# hail.net
KiCad netlist of a schematic drawn in EAGLE
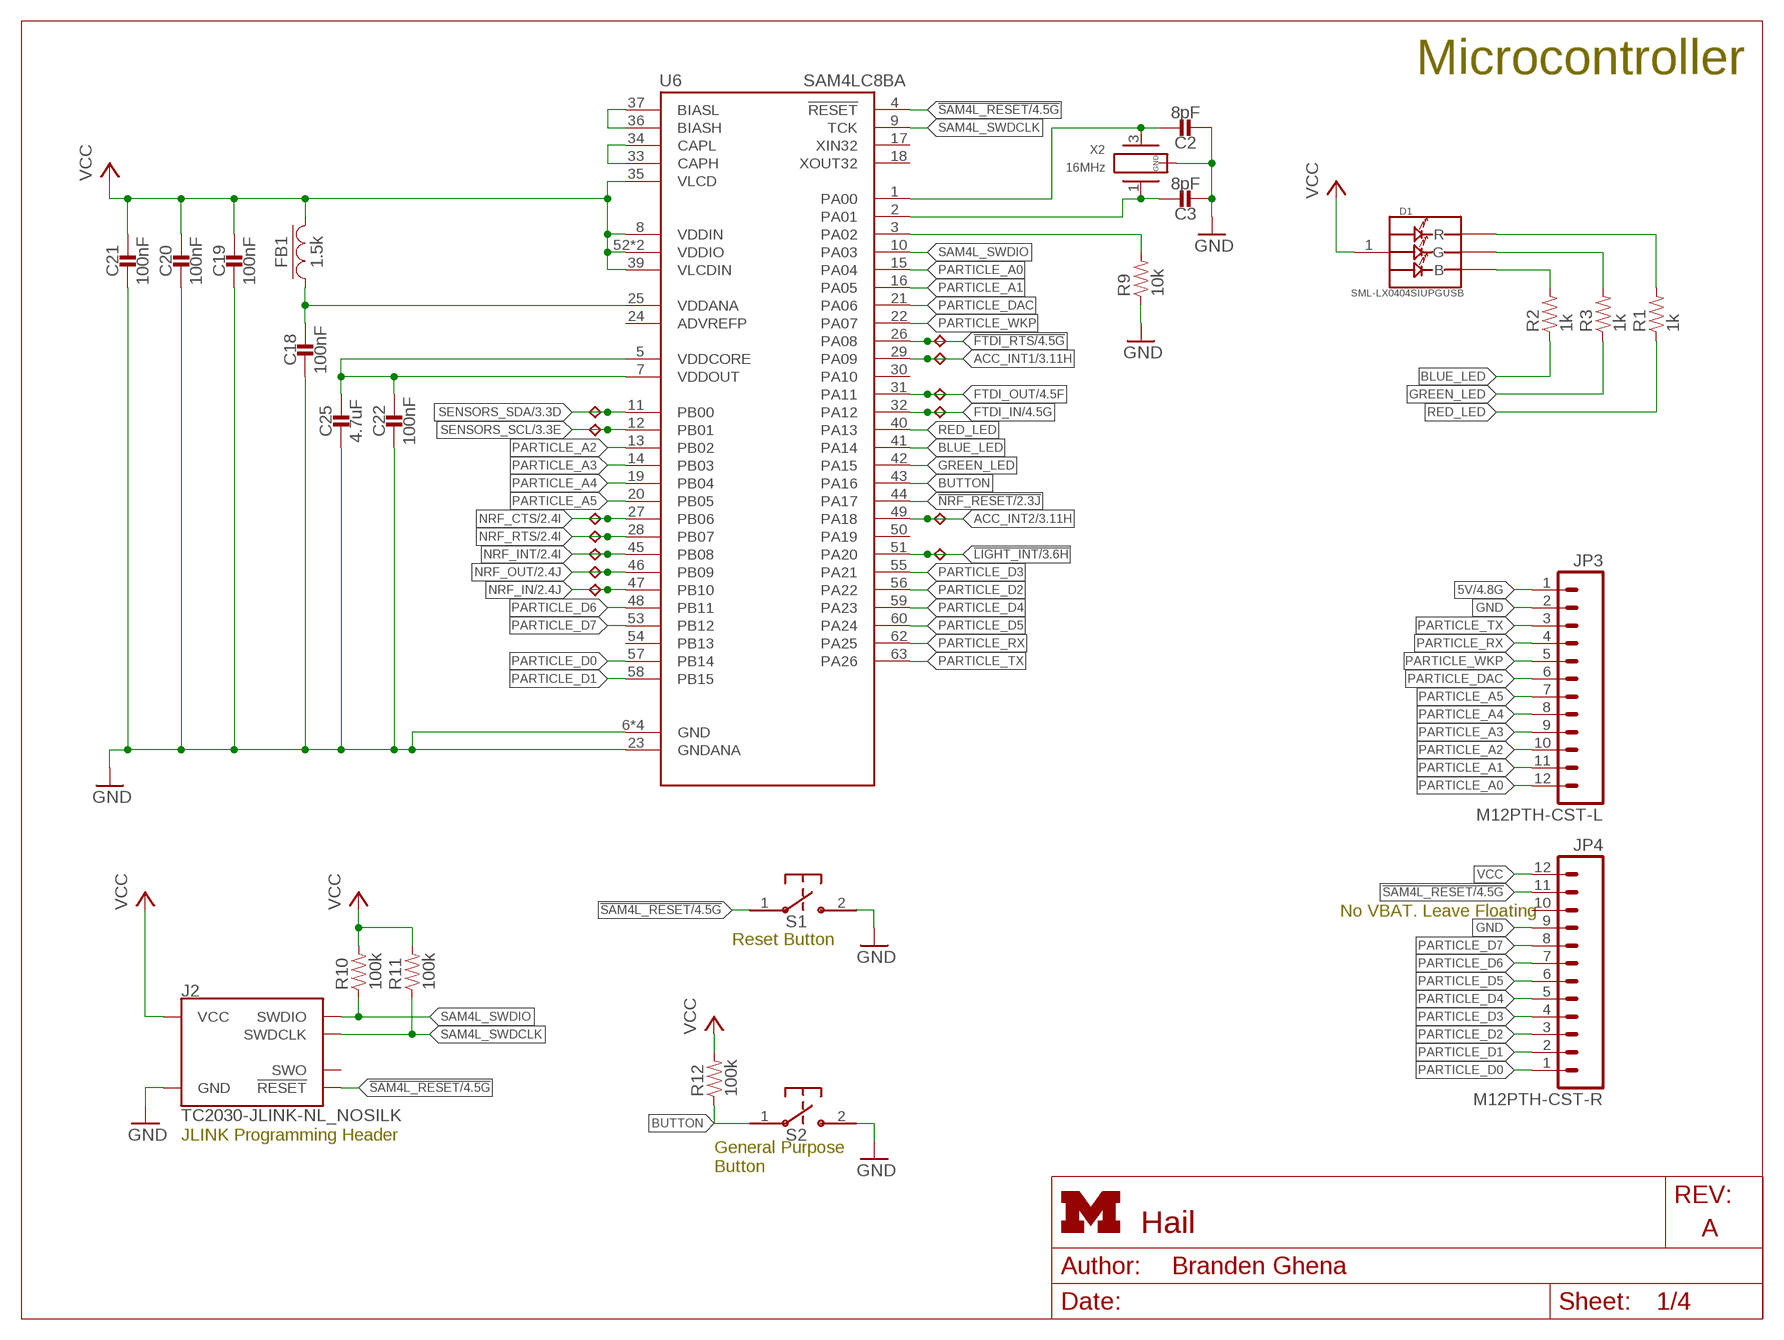
[diagram p0: schematic, sheet 1]
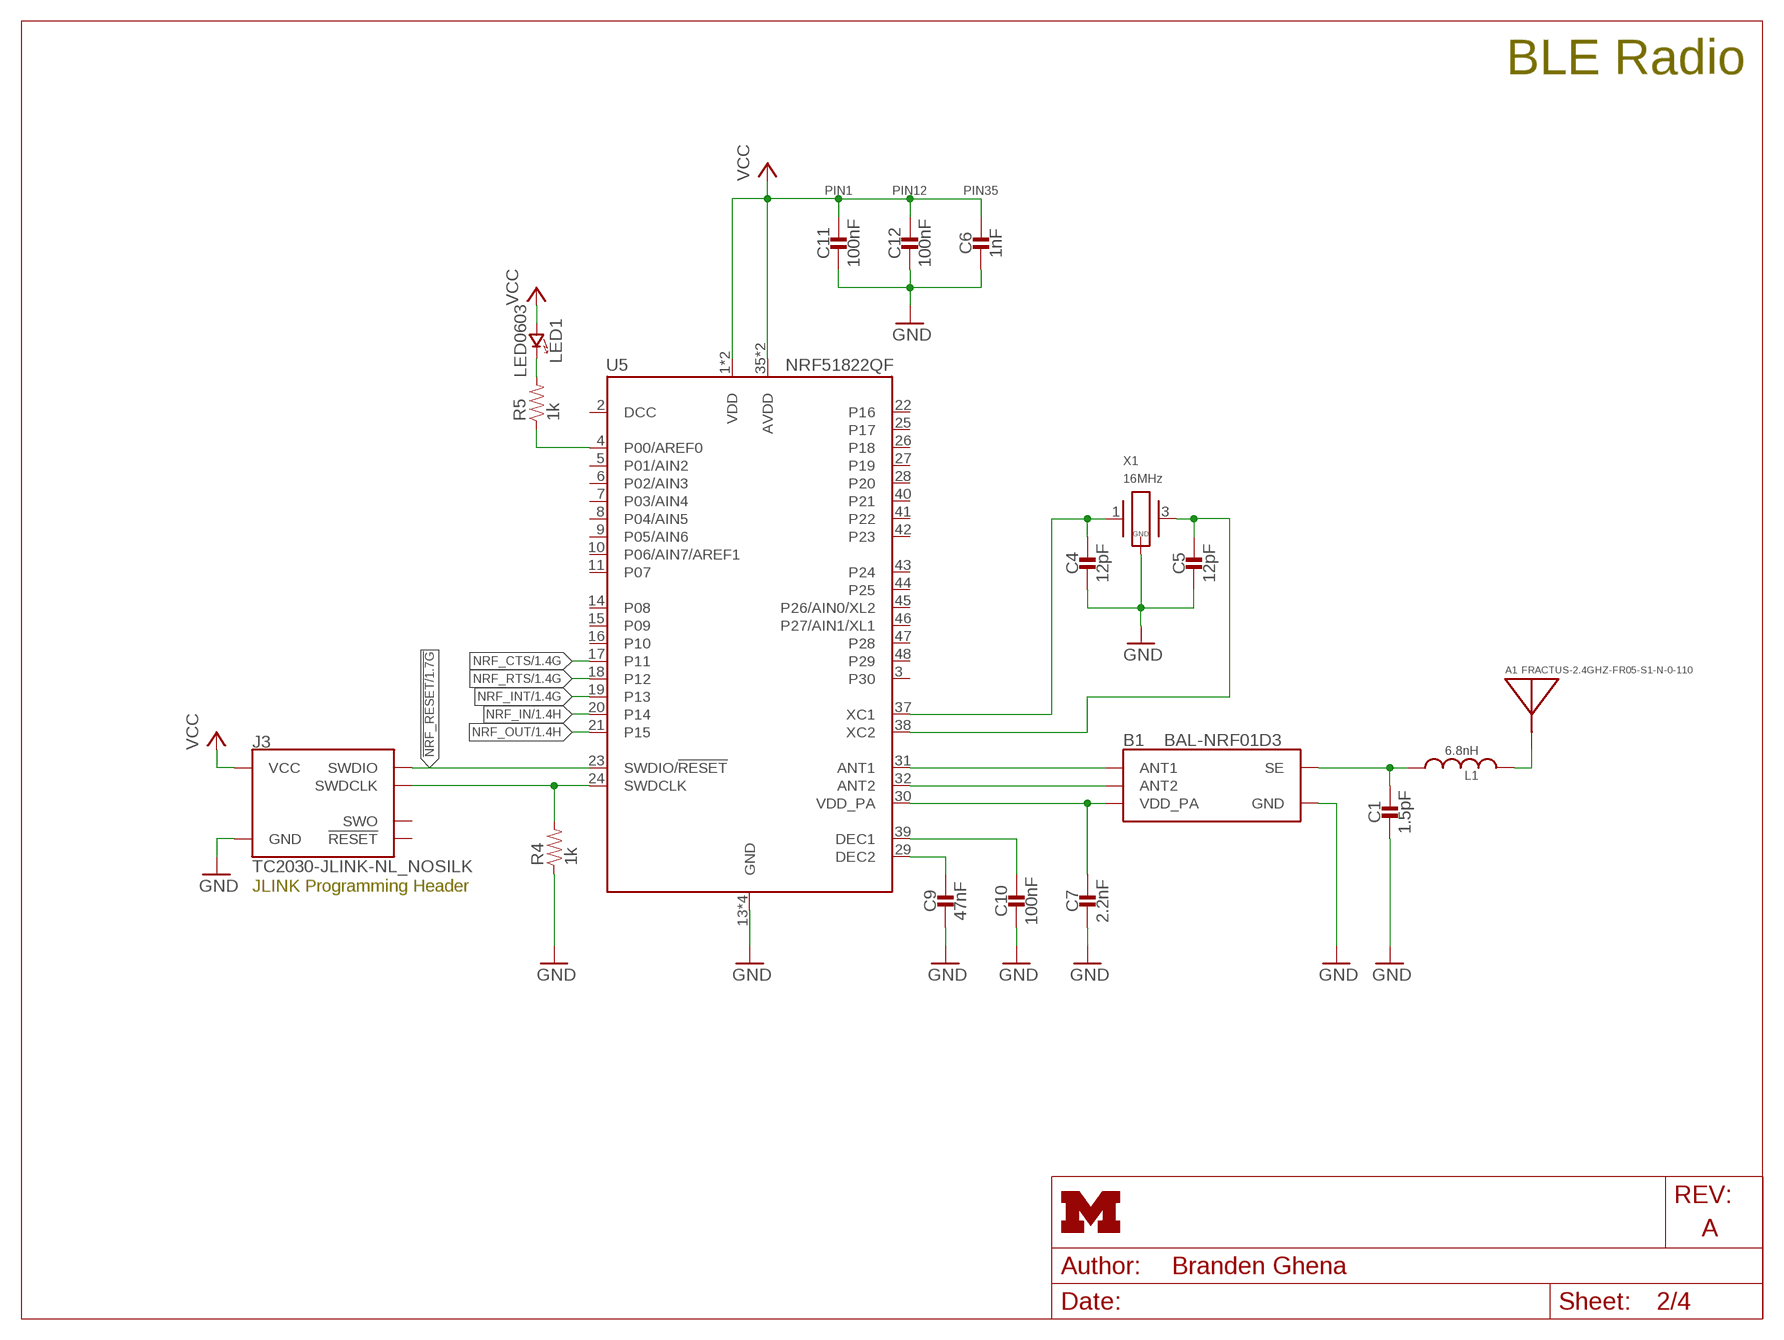
[diagram p1: schematic, sheet 2]
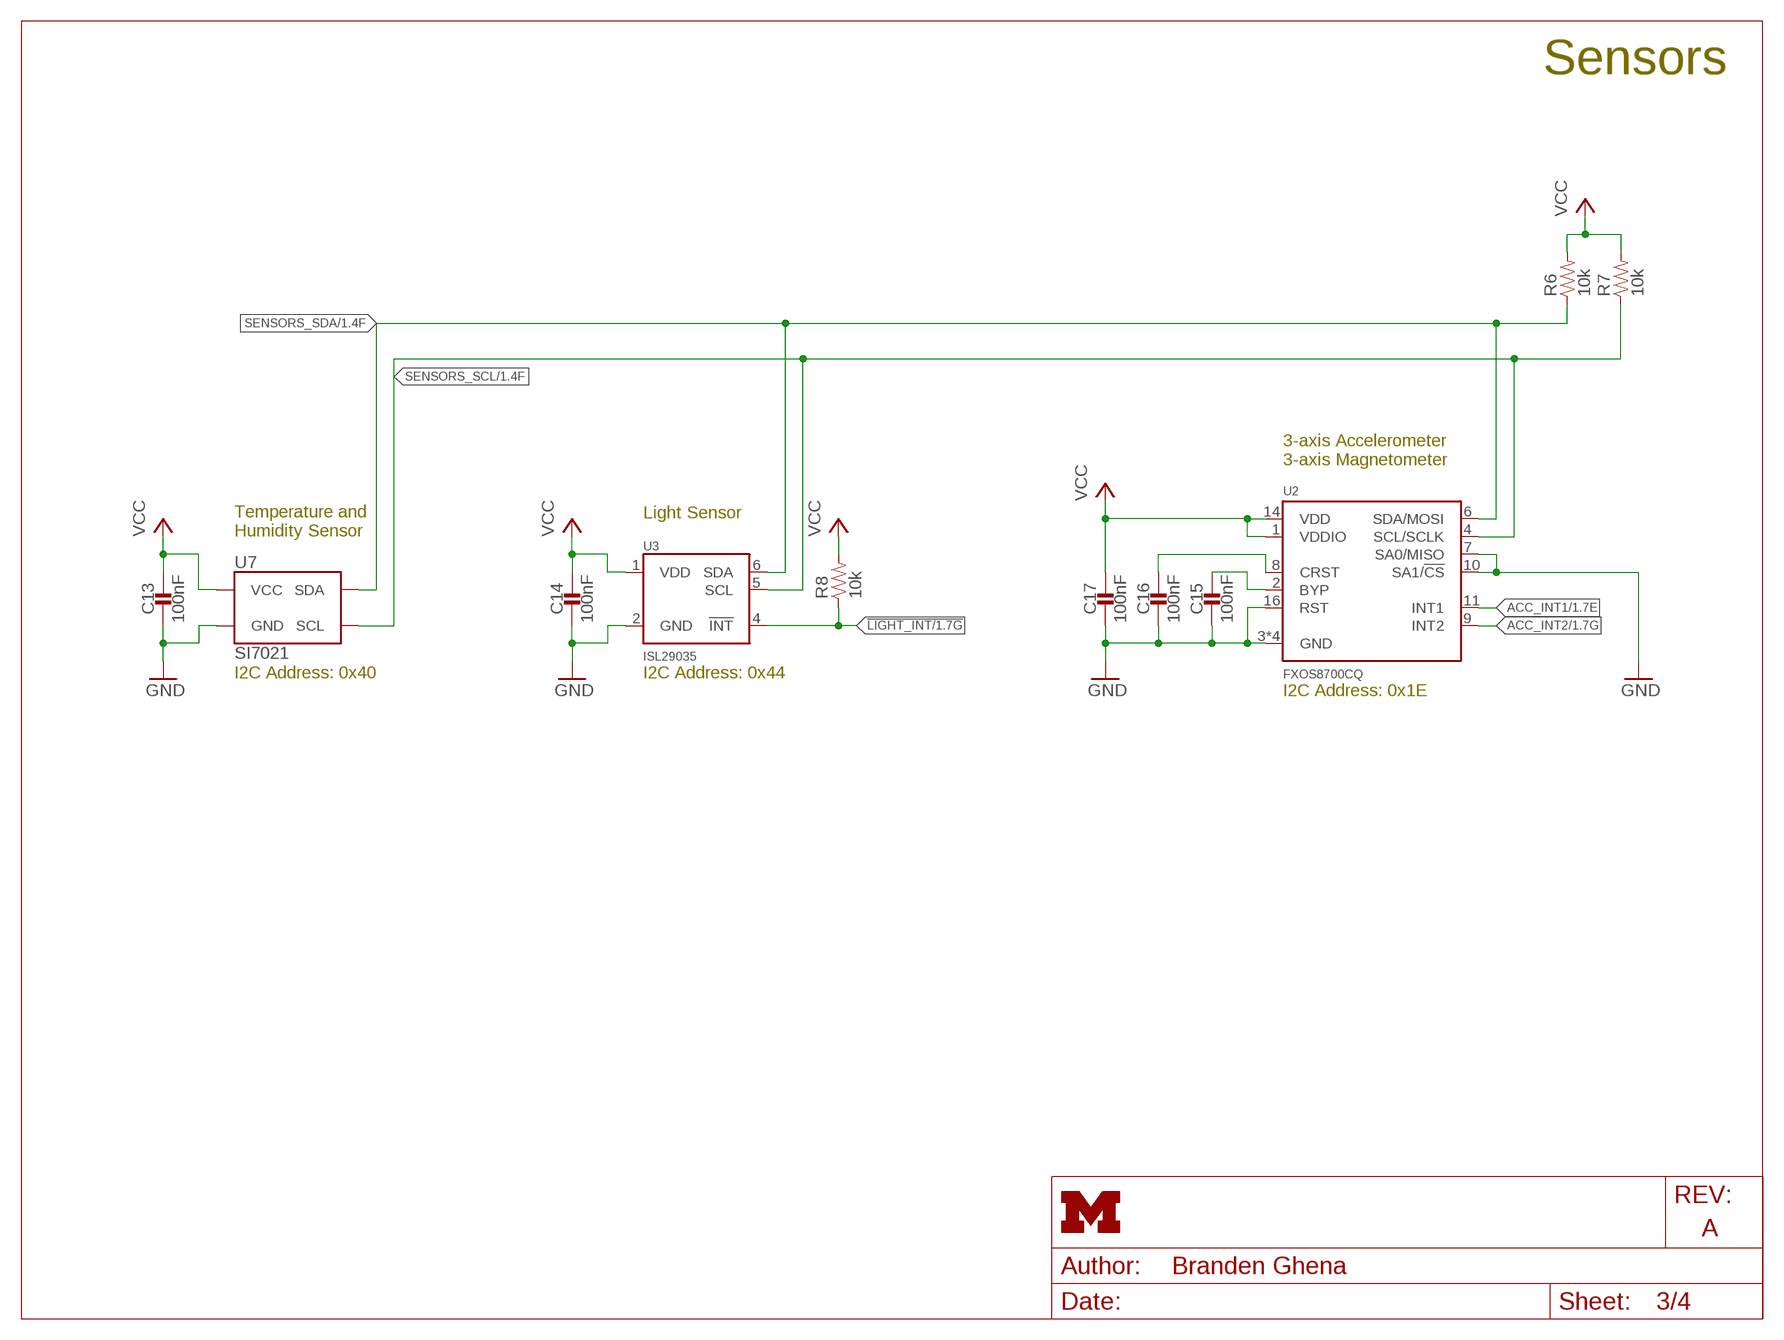
[diagram p2: schematic, sheet 3]
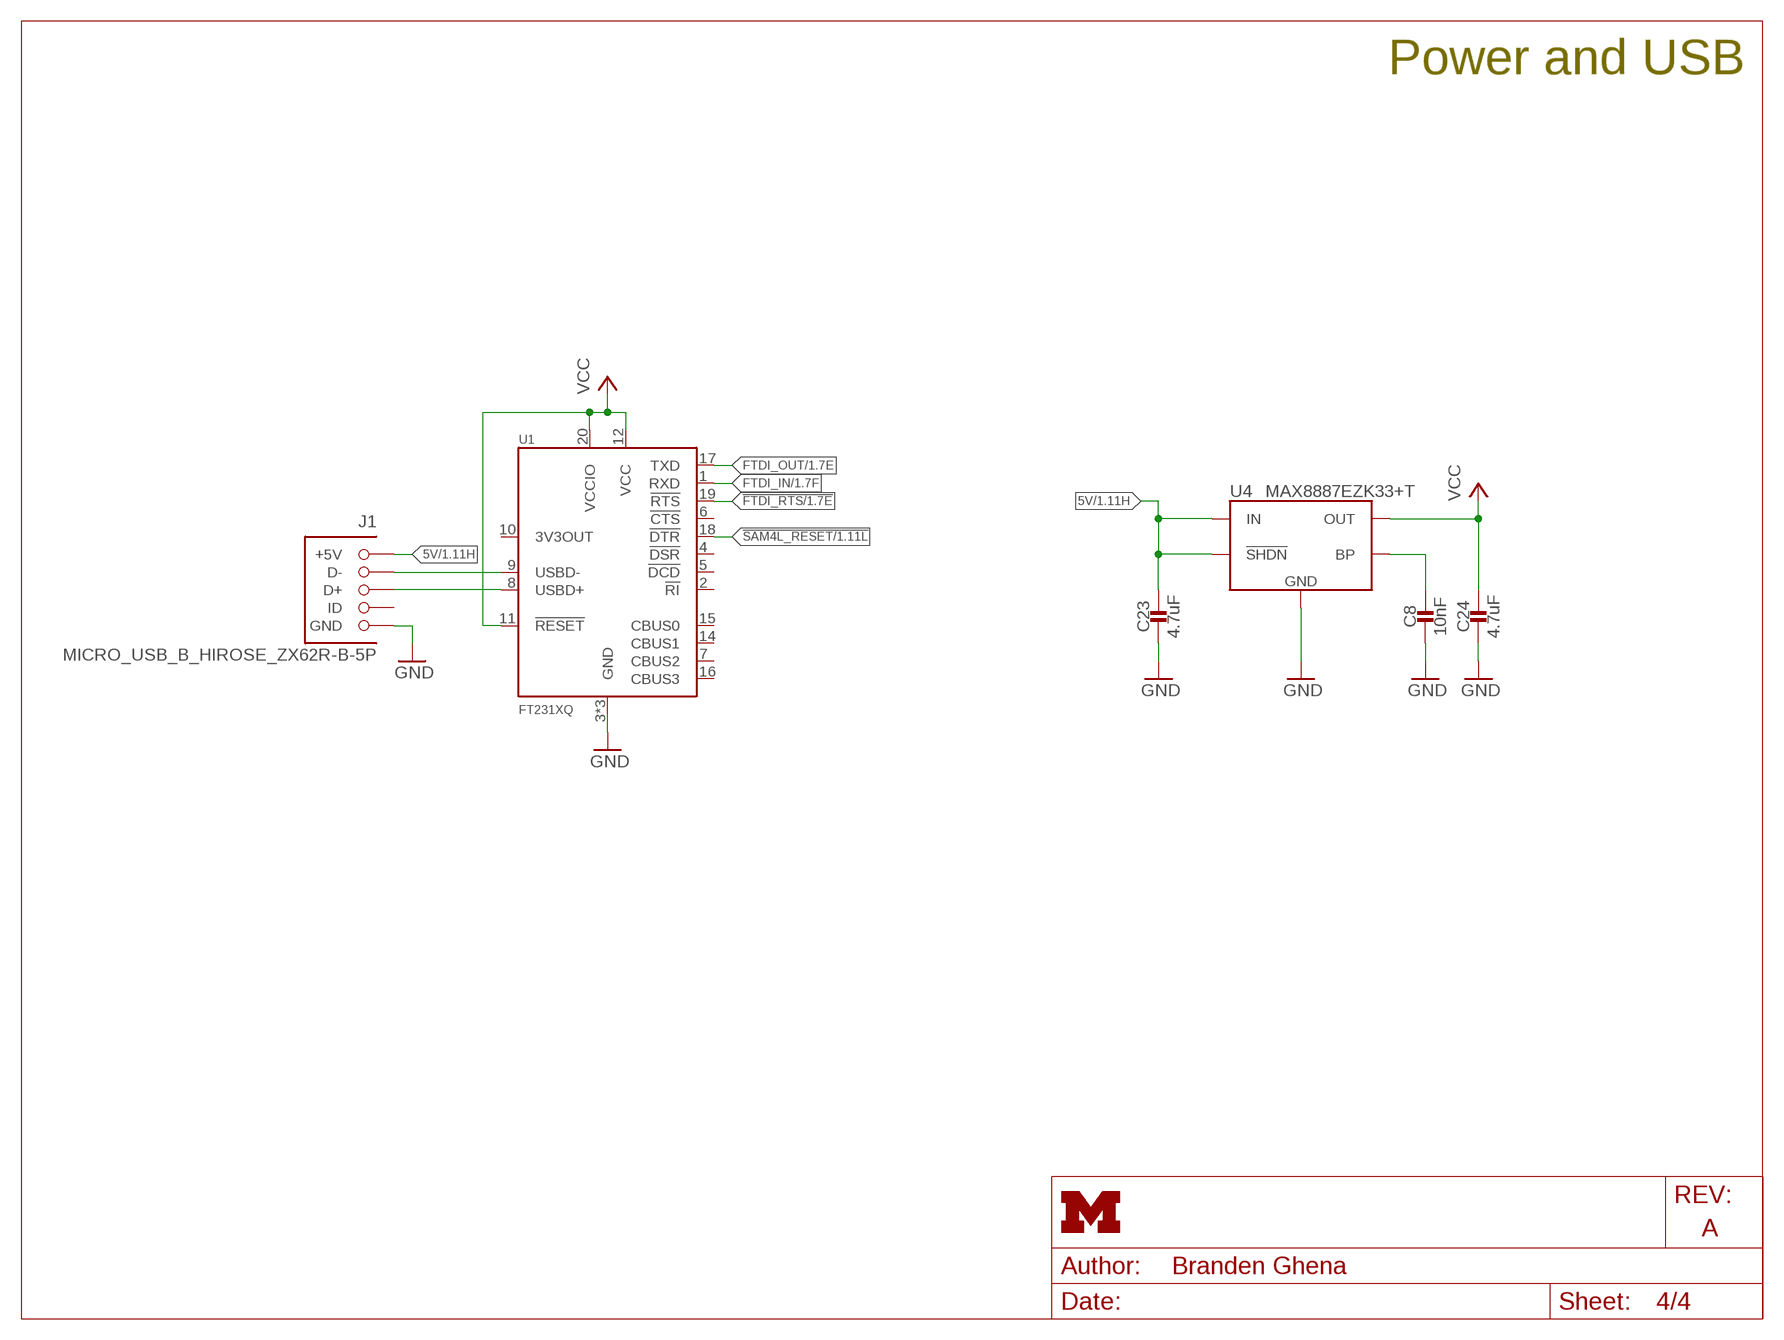
[diagram p3: schematic, sheet 4]

(export (version "E")
  (design (tool "Eeschema 10.0.6"))
  (components
    (comp (ref "C2")
      (value "8pF")
      (footprint "eagle-import:0402_CAP")
      (libsource (lib "eagle-import") (part "CAPACITOR0402_CAP"))
    )
    (comp (ref "C3")
      (value "8pF")
      (footprint "eagle-import:0402_CAP")
      (libsource (lib "eagle-import") (part "CAPACITOR0402_CAP"))
    )
    (comp (ref "C18")
      (value "100nF")
      (footprint "eagle-import:0402_CAP")
      (libsource (lib "eagle-import") (part "CAPACITOR0402_CAP"))
    )
    (comp (ref "C19")
      (value "100nF")
      (footprint "eagle-import:0402_CAP")
      (libsource (lib "eagle-import") (part "CAPACITOR0402_CAP"))
    )
    (comp (ref "C20")
      (value "100nF")
      (footprint "eagle-import:0402_CAP")
      (libsource (lib "eagle-import") (part "CAPACITOR0402_CAP"))
    )
    (comp (ref "C21")
      (value "100nF")
      (footprint "eagle-import:0402_CAP")
      (libsource (lib "eagle-import") (part "CAPACITOR0402_CAP"))
    )
    (comp (ref "C22")
      (value "100nF")
      (footprint "eagle-import:0402_CAP")
      (libsource (lib "eagle-import") (part "CAPACITOR0402_CAP"))
    )
    (comp (ref "C25")
      (value "4.7uF")
      (footprint "eagle-import:0402_CAP")
      (libsource (lib "eagle-import") (part "CAPACITOR0402_CAP"))
    )
    (comp (ref "D1")
      (value "SML-LX0404SIUPGUSB")
      (footprint "eagle-import:1MM_SQ_4PAD")
      (libsource (lib "eagle-import") (part "SML-LX0404SIUPGUSB"))
    )
    (comp (ref "FB1")
      (value "1.5k")
      (footprint "eagle-import:0402_CAP")
      (libsource (lib "eagle-import") (part "FERRITE_BEAD0402"))
    )
    (comp (ref "J2")
      (value "TC2030-JLINK-NL_NOSILK")
      (footprint "eagle-import:TC2030-IDC-NL_NOSILK")
      (libsource (lib "eagle-import") (part "TC2030-JLINK-NL_NOSILK"))
    )
    (comp (ref "JP3")
      (value "M12PTH-CST-L")
      (footprint "eagle-import:1X12-CASTELLATED")
      (libsource (lib "eagle-import") (part "M12PTH-CST-L"))
    )
    (comp (ref "JP4")
      (value "M12PTH-CST-R")
      (footprint "eagle-import:1X12-CASTELLATED")
      (libsource (lib "eagle-import") (part "M12PTH-CST-R"))
    )
    (comp (ref "R1")
      (value "1k")
      (footprint "eagle-import:0402_RES")
      (libsource (lib "eagle-import") (part "RESISTOR0402_RES"))
    )
    (comp (ref "R2")
      (value "1k")
      (footprint "eagle-import:0402_RES")
      (libsource (lib "eagle-import") (part "RESISTOR0402_RES"))
    )
    (comp (ref "R3")
      (value "1k")
      (footprint "eagle-import:0402_RES")
      (libsource (lib "eagle-import") (part "RESISTOR0402_RES"))
    )
    (comp (ref "R9")
      (value "10k")
      (footprint "eagle-import:0402_RES")
      (libsource (lib "eagle-import") (part "RESISTOR0402_RES"))
    )
    (comp (ref "R10")
      (value "100k")
      (footprint "eagle-import:0402_RES")
      (libsource (lib "eagle-import") (part "RESISTOR0402_RES"))
    )
    (comp (ref "R11")
      (value "100k")
      (footprint "eagle-import:0402_RES")
      (libsource (lib "eagle-import") (part "RESISTOR0402_RES"))
    )
    (comp (ref "R12")
      (value "100k")
      (footprint "eagle-import:0402_RES")
      (libsource (lib "eagle-import") (part "RESISTOR0402_RES"))
    )
    (comp (ref "S1")
      (value "B3U-1000P")
      (footprint "eagle-import:B3U-1000P")
      (libsource (lib "eagle-import") (part "B3U-1000P"))
    )
    (comp (ref "S2")
      (value "B3U-1000P")
      (footprint "eagle-import:B3U-1000P")
      (libsource (lib "eagle-import") (part "B3U-1000P"))
    )
    (comp (ref "TP1")
      (value "TPB1,27")
      (footprint "eagle-import:B1,27")
      (libsource (lib "eagle-import") (part "TPB1,27"))
    )
    (comp (ref "TP2")
      (value "TPB1,27")
      (footprint "eagle-import:B1,27")
      (libsource (lib "eagle-import") (part "TPB1,27"))
    )
    (comp (ref "TP3")
      (value "TPB1,27")
      (footprint "eagle-import:B1,27")
      (libsource (lib "eagle-import") (part "TPB1,27"))
    )
    (comp (ref "TP4")
      (value "TPB1,27")
      (footprint "eagle-import:B1,27")
      (libsource (lib "eagle-import") (part "TPB1,27"))
    )
    (comp (ref "TP5")
      (value "TPB1,27")
      (footprint "eagle-import:B1,27")
      (libsource (lib "eagle-import") (part "TPB1,27"))
    )
    (comp (ref "TP6")
      (value "TPB1,27")
      (footprint "eagle-import:B1,27")
      (libsource (lib "eagle-import") (part "TPB1,27"))
    )
    (comp (ref "TP7")
      (value "TPB1,27")
      (footprint "eagle-import:B1,27")
      (libsource (lib "eagle-import") (part "TPB1,27"))
    )
    (comp (ref "TP8")
      (value "TPB1,27")
      (footprint "eagle-import:B1,27")
      (libsource (lib "eagle-import") (part "TPB1,27"))
    )
    (comp (ref "TP9")
      (value "TPB1,27")
      (footprint "eagle-import:B1,27")
      (libsource (lib "eagle-import") (part "TPB1,27"))
    )
    (comp (ref "TP10")
      (value "TPB1,27")
      (footprint "eagle-import:B1,27")
      (libsource (lib "eagle-import") (part "TPB1,27"))
    )
    (comp (ref "TP11")
      (value "TPB1,27")
      (footprint "eagle-import:B1,27")
      (libsource (lib "eagle-import") (part "TPB1,27"))
    )
    (comp (ref "TP12")
      (value "TPB1,27")
      (footprint "eagle-import:B1,27")
      (libsource (lib "eagle-import") (part "TPB1,27"))
    )
    (comp (ref "TP13")
      (value "TPB1,27")
      (footprint "eagle-import:B1,27")
      (libsource (lib "eagle-import") (part "TPB1,27"))
    )
    (comp (ref "U6")
      (value "SAM4LC8BA")
      (footprint "eagle-import:QFN-64-9MM")
      (fields (field (name "DIGIKEY") "ATSAM4LC8BA-MURCT-ND"))
      (libsource (lib "eagle-import") (part "SAM4LC8BA"))
    )
    (comp (ref "X2")
      (value "16MHz")
      (footprint "eagle-import:FHXXX")
      (libsource (lib "eagle-import") (part "FH1600015"))
    )
    (comp (ref "A1")
      (value "FRACTUS-2.4GHZ-FR05-S1-N-0-110")
      (footprint "eagle-import:FRACTUS-ANTENNA-FR05-S1-N-0-110")
      (libsource (lib "eagle-import") (part "FRACTUS-2.4GHZ-FR05-S1-N-0-110"))
    )
    (comp (ref "B1")
      (value "BAL-NRF01D3")
      (footprint "eagle-import:BAL-NRF01D3")
      (libsource (lib "eagle-import") (part "BAL-NRF01D3"))
    )
    (comp (ref "C1")
      (value "1.5pF")
      (footprint "eagle-import:0402_CAP")
      (libsource (lib "eagle-import") (part "CAPACITOR0402_CAP"))
    )
    (comp (ref "C4")
      (value "12pF")
      (footprint "eagle-import:0402_CAP")
      (libsource (lib "eagle-import") (part "CAPACITOR0402_CAP"))
    )
    (comp (ref "C5")
      (value "12pF")
      (footprint "eagle-import:0402_CAP")
      (libsource (lib "eagle-import") (part "CAPACITOR0402_CAP"))
    )
    (comp (ref "C6")
      (value "1nF")
      (footprint "eagle-import:0402_CAP")
      (libsource (lib "eagle-import") (part "CAPACITOR0402_CAP"))
    )
    (comp (ref "C7")
      (value "2.2nF")
      (footprint "eagle-import:0402_CAP")
      (libsource (lib "eagle-import") (part "CAPACITOR0402_CAP"))
    )
    (comp (ref "C9")
      (value "47nF")
      (footprint "eagle-import:0402_CAP")
      (libsource (lib "eagle-import") (part "CAPACITOR0402_CAP"))
    )
    (comp (ref "C10")
      (value "100nF")
      (footprint "eagle-import:0402_CAP")
      (libsource (lib "eagle-import") (part "CAPACITOR0402_CAP"))
    )
    (comp (ref "C11")
      (value "100nF")
      (footprint "eagle-import:0402_CAP")
      (libsource (lib "eagle-import") (part "CAPACITOR0402_CAP"))
    )
    (comp (ref "C12")
      (value "100nF")
      (footprint "eagle-import:0402_CAP")
      (libsource (lib "eagle-import") (part "CAPACITOR0402_CAP"))
    )
    (comp (ref "J3")
      (value "TC2030-JLINK-NL_NOSILK")
      (footprint "eagle-import:TC2030-IDC-NL_NOSILK")
      (libsource (lib "eagle-import") (part "TC2030-JLINK-NL_NOSILK"))
    )
    (comp (ref "L1")
      (value "6.8nH")
      (footprint "eagle-import:0402_CAP")
      (libsource (lib "eagle-import") (part "INDUCTOR0402"))
    )
    (comp (ref "LED1")
      (value "LED0603")
      (footprint "eagle-import:LED-0603")
      (libsource (lib "eagle-import") (part "LED0603"))
    )
    (comp (ref "R4")
      (value "1k")
      (footprint "eagle-import:0402_RES")
      (libsource (lib "eagle-import") (part "RESISTOR0402_RES"))
    )
    (comp (ref "R5")
      (value "1k")
      (footprint "eagle-import:0402_RES")
      (libsource (lib "eagle-import") (part "RESISTOR0402_RES"))
    )
    (comp (ref "U5")
      (value "NRF51822QF")
      (footprint "eagle-import:QFN-48-6MM")
      (fields (field (name "DIGIKEY") "1490-1049-1-ND"))
      (libsource (lib "eagle-import") (part "NRF51822QF"))
    )
    (comp (ref "X1")
      (value "16MHz")
      (footprint "eagle-import:TXC-8Y")
      (libsource (lib "eagle-import") (part "TXC-8Y"))
    )
    (comp (ref "C8")
      (value "10nF")
      (footprint "eagle-import:0402_CAP")
      (libsource (lib "eagle-import") (part "CAPACITOR0402_CAP"))
    )
    (comp (ref "C23")
      (value "4.7uF")
      (footprint "eagle-import:0402_CAP")
      (libsource (lib "eagle-import") (part "CAPACITOR0402_CAP"))
    )
    (comp (ref "C24")
      (value "4.7uF")
      (footprint "eagle-import:0402_CAP")
      (libsource (lib "eagle-import") (part "CAPACITOR0402_CAP"))
    )
    (comp (ref "J1")
      (value "MICRO_USB_B_HIROSE_ZX62R-B-5P")
      (footprint "eagle-import:USB_MICRO_B-HIROSE-ZX62R-B-5P")
      (fields (field (name "DIGIKEY") "H125274CT-ND"))
      (libsource (lib "eagle-import") (part "MICRO_USB_B_HIROSE_ZX62R-B-5P"))
    )
    (comp (ref "U1")
      (value "FT231XQ")
      (footprint "eagle-import:QFN-20-4MM")
      (fields (field (name "MPN") "FT231XQ-R"))
      (libsource (lib "eagle-import") (part "FT231XQ"))
    )
    (comp (ref "U4")
      (value "MAX8887EZK33+T")
      (footprint "eagle-import:SOT-23-5")
      (libsource (lib "eagle-import") (part "MAX8887EZK33+T"))
    )
    (comp (ref "C13")
      (value "100nF")
      (footprint "eagle-import:0402_CAP")
      (libsource (lib "eagle-import") (part "CAPACITOR0402_CAP"))
    )
    (comp (ref "C14")
      (value "100nF")
      (footprint "eagle-import:0402_CAP")
      (libsource (lib "eagle-import") (part "CAPACITOR0402_CAP"))
    )
    (comp (ref "C15")
      (value "100nF")
      (footprint "eagle-import:0402_CAP")
      (libsource (lib "eagle-import") (part "CAPACITOR0402_CAP"))
    )
    (comp (ref "C16")
      (value "100nF")
      (footprint "eagle-import:0402_CAP")
      (libsource (lib "eagle-import") (part "CAPACITOR0402_CAP"))
    )
    (comp (ref "C17")
      (value "100nF")
      (footprint "eagle-import:0402_CAP")
      (libsource (lib "eagle-import") (part "CAPACITOR0402_CAP"))
    )
    (comp (ref "R6")
      (value "10k")
      (footprint "eagle-import:0402_RES")
      (libsource (lib "eagle-import") (part "RESISTOR0402_RES"))
    )
    (comp (ref "R7")
      (value "10k")
      (footprint "eagle-import:0402_RES")
      (libsource (lib "eagle-import") (part "RESISTOR0402_RES"))
    )
    (comp (ref "R8")
      (value "10k")
      (footprint "eagle-import:0402_RES")
      (libsource (lib "eagle-import") (part "RESISTOR0402_RES"))
    )
    (comp (ref "U2")
      (value "FXOS8700CQ")
      (footprint "eagle-import:QFN-16-3MM")
      (fields (field (name "MPN") "FXOS8700CQR1"))
      (libsource (lib "eagle-import") (part "FXOS8700CQ"))
    )
    (comp (ref "U3")
      (value "ISL29035")
      (footprint "eagle-import:ODFN-6-1.5MMX1.6MM")
      (fields (field (name "MPN") "ISL29035IROZ-T7"))
      (libsource (lib "eagle-import") (part "ISL29035"))
    )
    (comp (ref "U7")
      (value "SI7021")
      (footprint "eagle-import:DFN-6_3MM")
      (fields (field (name "DIGIKEY") "336-3141-ND"))
      (libsource (lib "eagle-import") (part "SI7021"))
    )
  )
  (nets
    (net (code "1") (name "5V") (class "Default")
      (node (ref "C23") (pin "1") (pinfunction "1_1") (pintype "bidirectional"))
      (node (ref "J1") (pin "1") (pinfunction "+5V_1") (pintype "bidirectional"))
      (node (ref "JP3") (pin "1") (pinfunction "12_1") (pintype "passive"))
      (node (ref "U4") (pin "1") (pinfunction "IN_1") (pintype "bidirectional"))
      (node (ref "U4") (pin "3") (pinfunction "~{SHDN}_3") (pintype "bidirectional"))
    )
    (net (code "2") (name "ACC_INT1") (class "Default")
      (node (ref "TP8") (pin "TP") (pinfunction "TP_TP") (pintype "input"))
      (node (ref "U2") (pin "11") (pinfunction "INT1_11") (pintype "bidirectional"))
      (node (ref "U6") (pin "29") (pinfunction "PA09_29") (pintype "bidirectional"))
    )
    (net (code "3") (name "ACC_INT2") (class "Default")
      (node (ref "TP9") (pin "TP") (pinfunction "TP_TP") (pintype "input"))
      (node (ref "U2") (pin "9") (pinfunction "INT2_9") (pintype "bidirectional"))
      (node (ref "U6") (pin "49") (pinfunction "PA18_49") (pintype "bidirectional"))
    )
    (net (code "4") (name "ADVREFP") (class "Default")
      (node (ref "U6") (pin "24") (pinfunction "ADVREFP_24") (pintype "power_in"))
    )
    (net (code "5") (name "BLUE_LED") (class "Default")
      (node (ref "R2") (pin "1") (pinfunction "1_1") (pintype "passive"))
      (node (ref "U6") (pin "41") (pinfunction "PA14_41") (pintype "bidirectional"))
    )
    (net (code "6") (name "BUTTON") (class "Default")
      (node (ref "R12") (pin "1") (pinfunction "1_1") (pintype "passive"))
      (node (ref "S2") (pin "1") (pinfunction "P$1_1") (pintype "passive"))
      (node (ref "U6") (pin "43") (pinfunction "PA16_43") (pintype "bidirectional"))
    )
    (net (code "7") (name "FTDI_IN") (class "Default")
      (node (ref "TP13") (pin "TP") (pinfunction "TP_TP") (pintype "input"))
      (node (ref "U1") (pin "1") (pinfunction "RXD_1") (pintype "bidirectional"))
      (node (ref "U6") (pin "32") (pinfunction "PA12_32") (pintype "bidirectional"))
    )
    (net (code "8") (name "FTDI_OUT") (class "Default")
      (node (ref "TP12") (pin "TP") (pinfunction "TP_TP") (pintype "input"))
      (node (ref "U1") (pin "17") (pinfunction "TXD_17") (pintype "bidirectional"))
      (node (ref "U6") (pin "31") (pinfunction "PA11_31") (pintype "bidirectional"))
    )
    (net (code "9") (name "GND") (class "Default")
      (node (ref "B1") (pin "GND") (pinfunction "GND_GND") (pintype "bidirectional"))
      (node (ref "C1") (pin "2") (pinfunction "2_2") (pintype "bidirectional"))
      (node (ref "C10") (pin "2") (pinfunction "2_2") (pintype "bidirectional"))
      (node (ref "C11") (pin "2") (pinfunction "2_2") (pintype "bidirectional"))
      (node (ref "C12") (pin "2") (pinfunction "2_2") (pintype "bidirectional"))
      (node (ref "C13") (pin "2") (pinfunction "2_2") (pintype "bidirectional"))
      (node (ref "C14") (pin "2") (pinfunction "2_2") (pintype "bidirectional"))
      (node (ref "C15") (pin "2") (pinfunction "2_2") (pintype "bidirectional"))
      (node (ref "C16") (pin "2") (pinfunction "2_2") (pintype "bidirectional"))
      (node (ref "C17") (pin "2") (pinfunction "2_2") (pintype "bidirectional"))
      (node (ref "C18") (pin "2") (pinfunction "2_2") (pintype "bidirectional"))
      (node (ref "C19") (pin "2") (pinfunction "2_2") (pintype "bidirectional"))
      (node (ref "C2") (pin "2") (pinfunction "2_2") (pintype "bidirectional"))
      (node (ref "C20") (pin "2") (pinfunction "2_2") (pintype "bidirectional"))
      (node (ref "C21") (pin "2") (pinfunction "2_2") (pintype "bidirectional"))
      (node (ref "C22") (pin "2") (pinfunction "2_2") (pintype "bidirectional"))
      (node (ref "C23") (pin "2") (pinfunction "2_2") (pintype "bidirectional"))
      (node (ref "C24") (pin "2") (pinfunction "2_2") (pintype "bidirectional"))
      (node (ref "C25") (pin "2") (pinfunction "2_2") (pintype "bidirectional"))
      (node (ref "C3") (pin "2") (pinfunction "2_2") (pintype "bidirectional"))
      (node (ref "C4") (pin "2") (pinfunction "2_2") (pintype "bidirectional"))
      (node (ref "C5") (pin "2") (pinfunction "2_2") (pintype "bidirectional"))
      (node (ref "C6") (pin "2") (pinfunction "2_2") (pintype "bidirectional"))
      (node (ref "C7") (pin "2") (pinfunction "2_2") (pintype "bidirectional"))
      (node (ref "C8") (pin "2") (pinfunction "2_2") (pintype "bidirectional"))
      (node (ref "C9") (pin "2") (pinfunction "2_2") (pintype "bidirectional"))
      (node (ref "J1") (pin "5") (pinfunction "GND_5") (pintype "bidirectional"))
      (node (ref "J2") (pin "5") (pinfunction "GND_5") (pintype "bidirectional"))
      (node (ref "J3") (pin "5") (pinfunction "GND_5") (pintype "bidirectional"))
      (node (ref "JP3") (pin "2") (pinfunction "11_2") (pintype "passive"))
      (node (ref "JP4") (pin "9") (pinfunction "9_9") (pintype "passive"))
      (node (ref "R4") (pin "1") (pinfunction "1_1") (pintype "passive"))
      (node (ref "R9") (pin "1") (pinfunction "1_1") (pintype "passive"))
      (node (ref "S1") (pin "2") (pinfunction "P$2_2") (pintype "passive"))
      (node (ref "S2") (pin "2") (pinfunction "P$2_2") (pintype "passive"))
      (node (ref "U1") (pin "13") (pinfunction "GND_13") (pintype "bidirectional"))
      (node (ref "U1") (pin "3") (pinfunction "GND_3") (pintype "bidirectional"))
      (node (ref "U1") (pin "GND") (pinfunction "GND_GND") (pintype "bidirectional"))
      (node (ref "U2") (pin "10") (pinfunction "SA1/~{CS}_10") (pintype "bidirectional"))
      (node (ref "U2") (pin "12") (pinfunction "GND_12") (pintype "bidirectional"))
      (node (ref "U2") (pin "13") (pinfunction "GND_13") (pintype "bidirectional"))
      (node (ref "U2") (pin "16") (pinfunction "RST_16") (pintype "bidirectional"))
      (node (ref "U2") (pin "3") (pinfunction "GND_3") (pintype "bidirectional"))
      (node (ref "U2") (pin "5") (pinfunction "GND_5") (pintype "bidirectional"))
      (node (ref "U2") (pin "7") (pinfunction "SA0/MISO_7") (pintype "bidirectional"))
      (node (ref "U3") (pin "2") (pinfunction "GND_2") (pintype "bidirectional"))
      (node (ref "U4") (pin "2") (pinfunction "GND_2") (pintype "bidirectional"))
      (node (ref "U5") (pin "13") (pinfunction "GND_13") (pintype "bidirectional"))
      (node (ref "U5") (pin "33") (pinfunction "GND_33") (pintype "bidirectional"))
      (node (ref "U5") (pin "34") (pinfunction "GND_34") (pintype "bidirectional"))
      (node (ref "U5") (pin "GND") (pinfunction "GND_GND") (pintype "bidirectional"))
      (node (ref "U6") (pin "23") (pinfunction "GNDANA_23") (pintype "power_in"))
      (node (ref "U6") (pin "38") (pinfunction "GND_38") (pintype "power_in"))
      (node (ref "U6") (pin "6") (pinfunction "GND_6") (pintype "power_in"))
      (node (ref "U6") (pin "64") (pinfunction "GND_64") (pintype "power_in"))
      (node (ref "U6") (pin "GND") (pinfunction "GND_GND") (pintype "power_in"))
      (node (ref "U7") (pin "2") (pinfunction "GND_2") (pintype "bidirectional"))
      (node (ref "X1") (pin "2") (pinfunction "GND_2") (pintype "bidirectional"))
      (node (ref "X1") (pin "4") (pinfunction "GND_4") (pintype "bidirectional"))
      (node (ref "X2") (pin "2") (pinfunction "GND_2") (pintype "bidirectional"))
      (node (ref "X2") (pin "4") (pinfunction "GND_4") (pintype "bidirectional"))
    )
    (net (code "10") (name "GREEN_LED") (class "Default")
      (node (ref "R3") (pin "1") (pinfunction "1_1") (pintype "passive"))
      (node (ref "U6") (pin "42") (pinfunction "PA15_42") (pintype "bidirectional"))
    )
    (net (code "11") (name "NRF_CTS") (class "Default")
      (node (ref "TP1") (pin "TP") (pinfunction "TP_TP") (pintype "input"))
      (node (ref "U5") (pin "17") (pinfunction "P11_17") (pintype "bidirectional"))
      (node (ref "U6") (pin "27") (pinfunction "PB06_27") (pintype "bidirectional"))
    )
    (net (code "12") (name "NRF_IN") (class "Default")
      (node (ref "TP5") (pin "TP") (pinfunction "TP_TP") (pintype "input"))
      (node (ref "U5") (pin "20") (pinfunction "P14_20") (pintype "bidirectional"))
      (node (ref "U6") (pin "47") (pinfunction "PB10_47") (pintype "bidirectional"))
    )
    (net (code "13") (name "NRF_INT") (class "Default")
      (node (ref "TP3") (pin "TP") (pinfunction "TP_TP") (pintype "input"))
      (node (ref "U5") (pin "19") (pinfunction "P13_19") (pintype "bidirectional"))
      (node (ref "U6") (pin "45") (pinfunction "PB08_45") (pintype "bidirectional"))
    )
    (net (code "14") (name "NRF_OUT") (class "Default")
      (node (ref "TP4") (pin "TP") (pinfunction "TP_TP") (pintype "input"))
      (node (ref "U5") (pin "21") (pinfunction "P15_21") (pintype "bidirectional"))
      (node (ref "U6") (pin "46") (pinfunction "PB09_46") (pintype "bidirectional"))
    )
    (net (code "15") (name "NRF_RTS") (class "Default")
      (node (ref "TP2") (pin "TP") (pinfunction "TP_TP") (pintype "input"))
      (node (ref "U5") (pin "18") (pinfunction "P12_18") (pintype "bidirectional"))
      (node (ref "U6") (pin "28") (pinfunction "PB07_28") (pintype "bidirectional"))
    )
    (net (code "16") (name "Net-(A1-ANTENNA)") (class "Default")
      (node (ref "A1") (pin "ANT") (pinfunction "ANTENNA_ANT") (pintype "bidirectional"))
      (node (ref "L1") (pin "2") (pinfunction "2_2") (pintype "bidirectional"))
    )
    (net (code "17") (name "Net-(B1-PadSE)") (class "Default")
      (node (ref "B1") (pin "SE") (pinfunction "SE_SE") (pintype "bidirectional"))
      (node (ref "C1") (pin "1") (pinfunction "1_1") (pintype "bidirectional"))
      (node (ref "L1") (pin "1") (pinfunction "1_1") (pintype "bidirectional"))
    )
    (net (code "18") (name "Net-(B1-VDD_PA)") (class "Default")
      (node (ref "B1") (pin "VCC") (pinfunction "VDD_PA_VCC") (pintype "bidirectional"))
      (node (ref "C7") (pin "1") (pinfunction "1_1") (pintype "bidirectional"))
      (node (ref "U5") (pin "30") (pinfunction "VDD_PA_30") (pintype "bidirectional"))
    )
    (net (code "19") (name "Net-(D1-B)") (class "Default")
      (node (ref "D1") (pin "3") (pinfunction "B_3") (pintype "output"))
      (node (ref "R2") (pin "2") (pinfunction "2_2") (pintype "passive"))
    )
    (net (code "20") (name "Net-(D1-G)") (class "Default")
      (node (ref "D1") (pin "4") (pinfunction "G_4") (pintype "output"))
      (node (ref "R3") (pin "2") (pinfunction "2_2") (pintype "passive"))
    )
    (net (code "21") (name "Net-(D1-R)") (class "Default")
      (node (ref "D1") (pin "2") (pinfunction "R_2") (pintype "output"))
      (node (ref "R1") (pin "2") (pinfunction "2_2") (pintype "passive"))
    )
    (net (code "22") (name "Net-(FB1-P$1)") (class "Default")
      (node (ref "C18") (pin "1") (pinfunction "1_1") (pintype "bidirectional"))
      (node (ref "FB1") (pin "1") (pinfunction "P$1_1") (pintype "bidirectional"))
      (node (ref "U6") (pin "25") (pinfunction "VDDANA_25") (pintype "power_in"))
    )
    (net (code "23") (name "Net-(J1-D+)") (class "Default")
      (node (ref "J1") (pin "3") (pinfunction "D+_3") (pintype "bidirectional"))
      (node (ref "U1") (pin "8") (pinfunction "USBD+_8") (pintype "bidirectional"))
    )
    (net (code "24") (name "Net-(J1-D-)") (class "Default")
      (node (ref "J1") (pin "2") (pinfunction "D-_2") (pintype "bidirectional"))
      (node (ref "U1") (pin "9") (pinfunction "USBD-_9") (pintype "bidirectional"))
    )
    (net (code "25") (name "Net-(J3-SWDCLK)") (class "Default")
      (node (ref "J3") (pin "4") (pinfunction "SWDCLK_4") (pintype "bidirectional"))
      (node (ref "R4") (pin "2") (pinfunction "2_2") (pintype "passive"))
      (node (ref "U5") (pin "24") (pinfunction "SWDCLK_24") (pintype "bidirectional"))
    )
    (net (code "26") (name "Net-(LED1-CATHODE)") (class "Default")
      (node (ref "LED1") (pin "C") (pinfunction "CATHODE_C") (pintype "bidirectional"))
      (node (ref "R5") (pin "2") (pinfunction "2_2") (pintype "passive"))
    )
    (net (code "27") (name "Net-(U2-BYP)") (class "Default")
      (node (ref "C15") (pin "1") (pinfunction "1_1") (pintype "bidirectional"))
      (node (ref "U2") (pin "2") (pinfunction "BYP_2") (pintype "bidirectional"))
    )
    (net (code "28") (name "Net-(U2-CRST)") (class "Default")
      (node (ref "C16") (pin "1") (pinfunction "1_1") (pintype "bidirectional"))
      (node (ref "U2") (pin "8") (pinfunction "CRST_8") (pintype "bidirectional"))
    )
    (net (code "29") (name "Net-(U4-BP)") (class "Default")
      (node (ref "C8") (pin "1") (pinfunction "1_1") (pintype "bidirectional"))
      (node (ref "U4") (pin "4") (pinfunction "BP_4") (pintype "bidirectional"))
    )
    (net (code "30") (name "Net-(U5-ANT1)") (class "Default")
      (node (ref "B1") (pin "ANT1") (pinfunction "ANT1_ANT1") (pintype "bidirectional"))
      (node (ref "U5") (pin "31") (pinfunction "ANT1_31") (pintype "bidirectional"))
    )
    (net (code "31") (name "Net-(U5-ANT2)") (class "Default")
      (node (ref "B1") (pin "ANT2") (pinfunction "ANT2_ANT2") (pintype "bidirectional"))
      (node (ref "U5") (pin "32") (pinfunction "ANT2_32") (pintype "bidirectional"))
    )
    (net (code "32") (name "Net-(U5-DEC1)") (class "Default")
      (node (ref "C10") (pin "1") (pinfunction "1_1") (pintype "bidirectional"))
      (node (ref "U5") (pin "39") (pinfunction "DEC1_39") (pintype "bidirectional"))
    )
    (net (code "33") (name "Net-(U5-DEC2)") (class "Default")
      (node (ref "C9") (pin "1") (pinfunction "1_1") (pintype "bidirectional"))
      (node (ref "U5") (pin "29") (pinfunction "DEC2_29") (pintype "bidirectional"))
    )
    (net (code "34") (name "Net-(U5-P00{slash}AREF0)") (class "Default")
      (node (ref "R5") (pin "1") (pinfunction "1_1") (pintype "passive"))
      (node (ref "U5") (pin "4") (pinfunction "P00/AREF0_4") (pintype "bidirectional"))
    )
    (net (code "35") (name "Net-(U5-XC1)") (class "Default")
      (node (ref "C4") (pin "1") (pinfunction "1_1") (pintype "bidirectional"))
      (node (ref "U5") (pin "37") (pinfunction "XC1_37") (pintype "bidirectional"))
      (node (ref "X1") (pin "1") (pinfunction "1_1") (pintype "bidirectional"))
    )
    (net (code "36") (name "Net-(U5-XC2)") (class "Default")
      (node (ref "C5") (pin "1") (pinfunction "1_1") (pintype "bidirectional"))
      (node (ref "U5") (pin "38") (pinfunction "XC2_38") (pintype "bidirectional"))
      (node (ref "X1") (pin "3") (pinfunction "2_3") (pintype "bidirectional"))
    )
    (net (code "37") (name "Net-(U6-BIASH)") (class "Default")
      (node (ref "U6") (pin "36") (pinfunction "BIASH_36") (pintype "bidirectional"))
      (node (ref "U6") (pin "37") (pinfunction "BIASL_37") (pintype "bidirectional"))
    )
    (net (code "38") (name "Net-(U6-CAPH)") (class "Default")
      (node (ref "U6") (pin "33") (pinfunction "CAPH_33") (pintype "bidirectional"))
      (node (ref "U6") (pin "34") (pinfunction "CAPL_34") (pintype "bidirectional"))
    )
    (net (code "39") (name "Net-(U6-PA00)") (class "Default")
      (node (ref "C2") (pin "1") (pinfunction "1_1") (pintype "bidirectional"))
      (node (ref "U6") (pin "1") (pinfunction "PA00_1") (pintype "bidirectional"))
      (node (ref "X2") (pin "3") (pinfunction "2_3") (pintype "bidirectional"))
    )
    (net (code "40") (name "Net-(U6-PA01)") (class "Default")
      (node (ref "C3") (pin "1") (pinfunction "1_1") (pintype "bidirectional"))
      (node (ref "U6") (pin "2") (pinfunction "PA01_2") (pintype "bidirectional"))
      (node (ref "X2") (pin "1") (pinfunction "1_1") (pintype "bidirectional"))
    )
    (net (code "41") (name "Net-(U6-PA02)") (class "Default")
      (node (ref "R9") (pin "2") (pinfunction "2_2") (pintype "passive"))
      (node (ref "U6") (pin "3") (pinfunction "PA02_3") (pintype "bidirectional"))
    )
    (net (code "42") (name "Net-(U6-VDDCORE)") (class "Default")
      (node (ref "C22") (pin "1") (pinfunction "1_1") (pintype "bidirectional"))
      (node (ref "C25") (pin "1") (pinfunction "1_1") (pintype "bidirectional"))
      (node (ref "U6") (pin "5") (pinfunction "VDDCORE_5") (pintype "power_in"))
      (node (ref "U6") (pin "7") (pinfunction "VDDOUT_7") (pintype "power_in"))
    )
    (net (code "43") (name "PARTICLE_A0") (class "Default")
      (node (ref "JP3") (pin "12") (pinfunction "1_12") (pintype "passive"))
      (node (ref "U6") (pin "15") (pinfunction "PA04_15") (pintype "bidirectional"))
    )
    (net (code "44") (name "PARTICLE_A1") (class "Default")
      (node (ref "JP3") (pin "11") (pinfunction "2_11") (pintype "passive"))
      (node (ref "U6") (pin "16") (pinfunction "PA05_16") (pintype "bidirectional"))
    )
    (net (code "45") (name "PARTICLE_A2") (class "Default")
      (node (ref "JP3") (pin "10") (pinfunction "3_10") (pintype "passive"))
      (node (ref "U6") (pin "13") (pinfunction "PB02_13") (pintype "bidirectional"))
    )
    (net (code "46") (name "PARTICLE_A3") (class "Default")
      (node (ref "JP3") (pin "9") (pinfunction "4_9") (pintype "passive"))
      (node (ref "U6") (pin "14") (pinfunction "PB03_14") (pintype "bidirectional"))
    )
    (net (code "47") (name "PARTICLE_A4") (class "Default")
      (node (ref "JP3") (pin "8") (pinfunction "5_8") (pintype "passive"))
      (node (ref "U6") (pin "19") (pinfunction "PB04_19") (pintype "bidirectional"))
    )
    (net (code "48") (name "PARTICLE_A5") (class "Default")
      (node (ref "JP3") (pin "7") (pinfunction "6_7") (pintype "passive"))
      (node (ref "U6") (pin "20") (pinfunction "PB05_20") (pintype "bidirectional"))
    )
    (net (code "49") (name "PARTICLE_D0") (class "Default")
      (node (ref "JP4") (pin "1") (pinfunction "1_1") (pintype "passive"))
      (node (ref "U6") (pin "57") (pinfunction "PB14_57") (pintype "bidirectional"))
    )
    (net (code "50") (name "PARTICLE_D1") (class "Default")
      (node (ref "JP4") (pin "2") (pinfunction "2_2") (pintype "passive"))
      (node (ref "U6") (pin "58") (pinfunction "PB15_58") (pintype "bidirectional"))
    )
    (net (code "51") (name "PARTICLE_D2") (class "Default")
      (node (ref "JP4") (pin "3") (pinfunction "3_3") (pintype "passive"))
      (node (ref "U6") (pin "56") (pinfunction "PA22_56") (pintype "bidirectional"))
    )
    (net (code "52") (name "PARTICLE_D3") (class "Default")
      (node (ref "JP4") (pin "4") (pinfunction "4_4") (pintype "passive"))
      (node (ref "U6") (pin "55") (pinfunction "PA21_55") (pintype "bidirectional"))
    )
    (net (code "53") (name "PARTICLE_D4") (class "Default")
      (node (ref "JP4") (pin "5") (pinfunction "5_5") (pintype "passive"))
      (node (ref "U6") (pin "59") (pinfunction "PA23_59") (pintype "bidirectional"))
    )
    (net (code "54") (name "PARTICLE_D5") (class "Default")
      (node (ref "JP4") (pin "6") (pinfunction "6_6") (pintype "passive"))
      (node (ref "U6") (pin "60") (pinfunction "PA24_60") (pintype "bidirectional"))
    )
    (net (code "55") (name "PARTICLE_D6") (class "Default")
      (node (ref "JP4") (pin "7") (pinfunction "7_7") (pintype "passive"))
      (node (ref "U6") (pin "48") (pinfunction "PB11_48") (pintype "bidirectional"))
    )
    (net (code "56") (name "PARTICLE_D7") (class "Default")
      (node (ref "JP4") (pin "8") (pinfunction "8_8") (pintype "passive"))
      (node (ref "U6") (pin "53") (pinfunction "PB12_53") (pintype "bidirectional"))
    )
    (net (code "57") (name "PARTICLE_DAC") (class "Default")
      (node (ref "JP3") (pin "6") (pinfunction "7_6") (pintype "passive"))
      (node (ref "U6") (pin "21") (pinfunction "PA06_21") (pintype "bidirectional"))
    )
    (net (code "58") (name "PARTICLE_RX") (class "Default")
      (node (ref "JP3") (pin "4") (pinfunction "9_4") (pintype "passive"))
      (node (ref "U6") (pin "62") (pinfunction "PA25_62") (pintype "bidirectional"))
    )
    (net (code "59") (name "PARTICLE_TX") (class "Default")
      (node (ref "JP3") (pin "3") (pinfunction "10_3") (pintype "passive"))
      (node (ref "U6") (pin "63") (pinfunction "PA26_63") (pintype "bidirectional"))
    )
    (net (code "60") (name "PARTICLE_WKP") (class "Default")
      (node (ref "JP3") (pin "5") (pinfunction "8_5") (pintype "passive"))
      (node (ref "U6") (pin "22") (pinfunction "PA07_22") (pintype "bidirectional"))
    )
    (net (code "61") (name "RED_LED") (class "Default")
      (node (ref "R1") (pin "1") (pinfunction "1_1") (pintype "passive"))
      (node (ref "U6") (pin "40") (pinfunction "PA13_40") (pintype "bidirectional"))
    )
    (net (code "62") (name "SAM4L_SWDCLK") (class "Default")
      (node (ref "J2") (pin "4") (pinfunction "SWDCLK_4") (pintype "bidirectional"))
      (node (ref "R11") (pin "1") (pinfunction "1_1") (pintype "passive"))
      (node (ref "U6") (pin "9") (pinfunction "TCK_9") (pintype "bidirectional"))
    )
    (net (code "63") (name "SAM4L_SWDIO") (class "Default")
      (node (ref "J2") (pin "2") (pinfunction "SWDIO_2") (pintype "bidirectional"))
      (node (ref "R10") (pin "1") (pinfunction "1_1") (pintype "passive"))
      (node (ref "U6") (pin "10") (pinfunction "PA03_10") (pintype "bidirectional"))
    )
    (net (code "64") (name "SENSORS_SCL") (class "Default")
      (node (ref "R7") (pin "1") (pinfunction "1_1") (pintype "passive"))
      (node (ref "TP7") (pin "TP") (pinfunction "TP_TP") (pintype "input"))
      (node (ref "U2") (pin "4") (pinfunction "SCL/SCLK_4") (pintype "bidirectional"))
      (node (ref "U3") (pin "5") (pinfunction "SCL_5") (pintype "bidirectional"))
      (node (ref "U6") (pin "12") (pinfunction "PB01_12") (pintype "bidirectional"))
      (node (ref "U7") (pin "6") (pinfunction "SCL_6") (pintype "bidirectional"))
    )
    (net (code "65") (name "SENSORS_SDA") (class "Default")
      (node (ref "R6") (pin "1") (pinfunction "1_1") (pintype "passive"))
      (node (ref "TP6") (pin "TP") (pinfunction "TP_TP") (pintype "input"))
      (node (ref "U2") (pin "6") (pinfunction "SDA/MOSI_6") (pintype "bidirectional"))
      (node (ref "U3") (pin "6") (pinfunction "SDA_6") (pintype "bidirectional"))
      (node (ref "U6") (pin "11") (pinfunction "PB00_11") (pintype "bidirectional"))
      (node (ref "U7") (pin "1") (pinfunction "SDA_1") (pintype "bidirectional"))
    )
    (net (code "66") (name "VCC") (class "Default")
      (node (ref "C11") (pin "1") (pinfunction "1_1") (pintype "bidirectional"))
      (node (ref "C12") (pin "1") (pinfunction "1_1") (pintype "bidirectional"))
      (node (ref "C13") (pin "1") (pinfunction "1_1") (pintype "bidirectional"))
      (node (ref "C14") (pin "1") (pinfunction "1_1") (pintype "bidirectional"))
      (node (ref "C17") (pin "1") (pinfunction "1_1") (pintype "bidirectional"))
      (node (ref "C19") (pin "1") (pinfunction "1_1") (pintype "bidirectional"))
      (node (ref "C20") (pin "1") (pinfunction "1_1") (pintype "bidirectional"))
      (node (ref "C21") (pin "1") (pinfunction "1_1") (pintype "bidirectional"))
      (node (ref "C24") (pin "1") (pinfunction "1_1") (pintype "bidirectional"))
      (node (ref "C6") (pin "1") (pinfunction "1_1") (pintype "bidirectional"))
      (node (ref "D1") (pin "1") (pinfunction "VDD_1") (pintype "bidirectional"))
      (node (ref "FB1") (pin "2") (pinfunction "P$2_2") (pintype "bidirectional"))
      (node (ref "J2") (pin "1") (pinfunction "VCC_1") (pintype "bidirectional"))
      (node (ref "J3") (pin "1") (pinfunction "VCC_1") (pintype "bidirectional"))
      (node (ref "JP4") (pin "12") (pinfunction "12_12") (pintype "passive"))
      (node (ref "LED1") (pin "A") (pinfunction "ANODE_A") (pintype "bidirectional"))
      (node (ref "R10") (pin "2") (pinfunction "2_2") (pintype "passive"))
      (node (ref "R11") (pin "2") (pinfunction "2_2") (pintype "passive"))
      (node (ref "R12") (pin "2") (pinfunction "2_2") (pintype "passive"))
      (node (ref "R6") (pin "2") (pinfunction "2_2") (pintype "passive"))
      (node (ref "R7") (pin "2") (pinfunction "2_2") (pintype "passive"))
      (node (ref "R8") (pin "2") (pinfunction "2_2") (pintype "passive"))
      (node (ref "U1") (pin "11") (pinfunction "~{RESET}_11") (pintype "bidirectional"))
      (node (ref "U1") (pin "12") (pinfunction "VCC_12") (pintype "bidirectional"))
      (node (ref "U1") (pin "20") (pinfunction "VCCIO_20") (pintype "bidirectional"))
      (node (ref "U2") (pin "1") (pinfunction "VDDIO_1") (pintype "bidirectional"))
      (node (ref "U2") (pin "14") (pinfunction "VDD_14") (pintype "bidirectional"))
      (node (ref "U3") (pin "1") (pinfunction "VDD_1") (pintype "bidirectional"))
      (node (ref "U4") (pin "5") (pinfunction "OUT_5") (pintype "bidirectional"))
      (node (ref "U5") (pin "1") (pinfunction "VDD_1") (pintype "bidirectional"))
      (node (ref "U5") (pin "12") (pinfunction "VDD_12") (pintype "bidirectional"))
      (node (ref "U5") (pin "35") (pinfunction "AVDD_35") (pintype "bidirectional"))
      (node (ref "U5") (pin "36") (pinfunction "AVDD_36") (pintype "bidirectional"))
      (node (ref "U6") (pin "35") (pinfunction "VLCD_35") (pintype "bidirectional"))
      (node (ref "U6") (pin "39") (pinfunction "VLCDIN_39") (pintype "power_in"))
      (node (ref "U6") (pin "52") (pinfunction "VDDIO_52") (pintype "power_in"))
      (node (ref "U6") (pin "61") (pinfunction "VDDIO_61") (pintype "power_in"))
      (node (ref "U6") (pin "8") (pinfunction "VDDIN_8") (pintype "power_in"))
      (node (ref "U7") (pin "5") (pinfunction "VCC_5") (pintype "bidirectional"))
    )
    (net (code "67") (name "unconnected-(J1-ID-Pad4)") (class "Default")
      (node (ref "J1") (pin "4") (pinfunction "ID_4") (pintype "bidirectional"))
    )
    (net (code "68") (name "unconnected-(J2-SWO-Pad6)") (class "Default")
      (node (ref "J2") (pin "6") (pinfunction "SWO_6") (pintype "bidirectional"))
    )
    (net (code "69") (name "unconnected-(J3-SWO-Pad6)") (class "Default")
      (node (ref "J3") (pin "6") (pinfunction "SWO_6") (pintype "bidirectional"))
    )
    (net (code "70") (name "unconnected-(J3-~{RESET}-Pad3)") (class "Default")
      (node (ref "J3") (pin "3") (pinfunction "~{RESET}_3") (pintype "bidirectional"))
    )
    (net (code "71") (name "unconnected-(JP4-Pad10)") (class "Default")
      (node (ref "JP4") (pin "10") (pinfunction "10_10") (pintype "passive"))
    )
    (net (code "72") (name "unconnected-(U1-3V3OUT-Pad10)") (class "Default")
      (node (ref "U1") (pin "10") (pinfunction "3V3OUT_10") (pintype "bidirectional"))
    )
    (net (code "73") (name "unconnected-(U1-CBUS0-Pad15)") (class "Default")
      (node (ref "U1") (pin "15") (pinfunction "CBUS0_15") (pintype "bidirectional"))
    )
    (net (code "74") (name "unconnected-(U1-CBUS1-Pad14)") (class "Default")
      (node (ref "U1") (pin "14") (pinfunction "CBUS1_14") (pintype "bidirectional"))
    )
    (net (code "75") (name "unconnected-(U1-CBUS2-Pad7)") (class "Default")
      (node (ref "U1") (pin "7") (pinfunction "CBUS2_7") (pintype "bidirectional"))
    )
    (net (code "76") (name "unconnected-(U1-CBUS3-Pad16)") (class "Default")
      (node (ref "U1") (pin "16") (pinfunction "CBUS3_16") (pintype "bidirectional"))
    )
    (net (code "77") (name "unconnected-(U1-~{CTS}-Pad6)") (class "Default")
      (node (ref "U1") (pin "6") (pinfunction "~{CTS}_6") (pintype "bidirectional"))
    )
    (net (code "78") (name "unconnected-(U1-~{DCD}-Pad5)") (class "Default")
      (node (ref "U1") (pin "5") (pinfunction "~{DCD}_5") (pintype "bidirectional"))
    )
    (net (code "79") (name "unconnected-(U1-~{DSR}-Pad4)") (class "Default")
      (node (ref "U1") (pin "4") (pinfunction "~{DSR}_4") (pintype "bidirectional"))
    )
    (net (code "80") (name "unconnected-(U1-~{RI}-Pad2)") (class "Default")
      (node (ref "U1") (pin "2") (pinfunction "~{RI}_2") (pintype "bidirectional"))
    )
    (net (code "81") (name "unconnected-(U5-DCC-Pad2)") (class "Default")
      (node (ref "U5") (pin "2") (pinfunction "DCC_2") (pintype "bidirectional"))
    )
    (net (code "82") (name "unconnected-(U5-P01{slash}AIN2-Pad5)") (class "Default")
      (node (ref "U5") (pin "5") (pinfunction "P01/AIN2_5") (pintype "bidirectional"))
    )
    (net (code "83") (name "unconnected-(U5-P02{slash}AIN3-Pad6)") (class "Default")
      (node (ref "U5") (pin "6") (pinfunction "P02/AIN3_6") (pintype "bidirectional"))
    )
    (net (code "84") (name "unconnected-(U5-P03{slash}AIN4-Pad7)") (class "Default")
      (node (ref "U5") (pin "7") (pinfunction "P03/AIN4_7") (pintype "bidirectional"))
    )
    (net (code "85") (name "unconnected-(U5-P04{slash}AIN5-Pad8)") (class "Default")
      (node (ref "U5") (pin "8") (pinfunction "P04/AIN5_8") (pintype "bidirectional"))
    )
    (net (code "86") (name "unconnected-(U5-P05{slash}AIN6-Pad9)") (class "Default")
      (node (ref "U5") (pin "9") (pinfunction "P05/AIN6_9") (pintype "bidirectional"))
    )
    (net (code "87") (name "unconnected-(U5-P06{slash}AIN7{slash}AREF1-Pad10)") (class "Default")
      (node (ref "U5") (pin "10") (pinfunction "P06/AIN7/AREF1_10") (pintype "bidirectional"))
    )
    (net (code "88") (name "unconnected-(U5-P07-Pad11)") (class "Default")
      (node (ref "U5") (pin "11") (pinfunction "P07_11") (pintype "bidirectional"))
    )
    (net (code "89") (name "unconnected-(U5-P08-Pad14)") (class "Default")
      (node (ref "U5") (pin "14") (pinfunction "P08_14") (pintype "bidirectional"))
    )
    (net (code "90") (name "unconnected-(U5-P09-Pad15)") (class "Default")
      (node (ref "U5") (pin "15") (pinfunction "P09_15") (pintype "bidirectional"))
    )
    (net (code "91") (name "unconnected-(U5-P10-Pad16)") (class "Default")
      (node (ref "U5") (pin "16") (pinfunction "P10_16") (pintype "bidirectional"))
    )
    (net (code "92") (name "unconnected-(U5-P16-Pad22)") (class "Default")
      (node (ref "U5") (pin "22") (pinfunction "P16_22") (pintype "bidirectional"))
    )
    (net (code "93") (name "unconnected-(U5-P17-Pad25)") (class "Default")
      (node (ref "U5") (pin "25") (pinfunction "P17_25") (pintype "bidirectional"))
    )
    (net (code "94") (name "unconnected-(U5-P18-Pad26)") (class "Default")
      (node (ref "U5") (pin "26") (pinfunction "P18_26") (pintype "bidirectional"))
    )
    (net (code "95") (name "unconnected-(U5-P19-Pad27)") (class "Default")
      (node (ref "U5") (pin "27") (pinfunction "P19_27") (pintype "bidirectional"))
    )
    (net (code "96") (name "unconnected-(U5-P20-Pad28)") (class "Default")
      (node (ref "U5") (pin "28") (pinfunction "P20_28") (pintype "bidirectional"))
    )
    (net (code "97") (name "unconnected-(U5-P21-Pad40)") (class "Default")
      (node (ref "U5") (pin "40") (pinfunction "P21_40") (pintype "bidirectional"))
    )
    (net (code "98") (name "unconnected-(U5-P22-Pad41)") (class "Default")
      (node (ref "U5") (pin "41") (pinfunction "P22_41") (pintype "bidirectional"))
    )
    (net (code "99") (name "unconnected-(U5-P23-Pad42)") (class "Default")
      (node (ref "U5") (pin "42") (pinfunction "P23_42") (pintype "bidirectional"))
    )
    (net (code "100") (name "unconnected-(U5-P24-Pad43)") (class "Default")
      (node (ref "U5") (pin "43") (pinfunction "P24_43") (pintype "bidirectional"))
    )
    (net (code "101") (name "unconnected-(U5-P25-Pad44)") (class "Default")
      (node (ref "U5") (pin "44") (pinfunction "P25_44") (pintype "bidirectional"))
    )
    (net (code "102") (name "unconnected-(U5-P26{slash}AIN0{slash}XL2-Pad45)") (class "Default")
      (node (ref "U5") (pin "45") (pinfunction "P26/AIN0/XL2_45") (pintype "bidirectional"))
    )
    (net (code "103") (name "unconnected-(U5-P27{slash}AIN1{slash}XL1-Pad46)") (class "Default")
      (node (ref "U5") (pin "46") (pinfunction "P27/AIN1/XL1_46") (pintype "bidirectional"))
    )
    (net (code "104") (name "unconnected-(U5-P28-Pad47)") (class "Default")
      (node (ref "U5") (pin "47") (pinfunction "P28_47") (pintype "bidirectional"))
    )
    (net (code "105") (name "unconnected-(U5-P29-Pad48)") (class "Default")
      (node (ref "U5") (pin "48") (pinfunction "P29_48") (pintype "bidirectional"))
    )
    (net (code "106") (name "unconnected-(U5-P30-Pad3)") (class "Default")
      (node (ref "U5") (pin "3") (pinfunction "P30_3") (pintype "bidirectional"))
    )
    (net (code "107") (name "unconnected-(U6-PA10-Pad30)") (class "Default")
      (node (ref "U6") (pin "30") (pinfunction "PA10_30") (pintype "bidirectional"))
    )
    (net (code "108") (name "unconnected-(U6-PA19-Pad50)") (class "Default")
      (node (ref "U6") (pin "50") (pinfunction "PA19_50") (pintype "bidirectional"))
    )
    (net (code "109") (name "unconnected-(U6-PB13-Pad54)") (class "Default")
      (node (ref "U6") (pin "54") (pinfunction "PB13_54") (pintype "bidirectional"))
    )
    (net (code "110") (name "unconnected-(U6-XIN32-Pad17)") (class "Default")
      (node (ref "U6") (pin "17") (pinfunction "XIN32_17") (pintype "bidirectional"))
    )
    (net (code "111") (name "unconnected-(U6-XOUT32-Pad18)") (class "Default")
      (node (ref "U6") (pin "18") (pinfunction "XOUT32_18") (pintype "bidirectional"))
    )
    (net (code "112") (name "~{FTDI_RTS}") (class "Default")
      (node (ref "TP11") (pin "TP") (pinfunction "TP_TP") (pintype "input"))
      (node (ref "U1") (pin "19") (pinfunction "~{RTS}_19") (pintype "bidirectional"))
      (node (ref "U6") (pin "26") (pinfunction "PA08_26") (pintype "bidirectional"))
    )
    (net (code "113") (name "~{LIGHT_INT}") (class "Default")
      (node (ref "R8") (pin "1") (pinfunction "1_1") (pintype "passive"))
      (node (ref "TP10") (pin "TP") (pinfunction "TP_TP") (pintype "input"))
      (node (ref "U3") (pin "4") (pinfunction "~{INT}_4") (pintype "bidirectional"))
      (node (ref "U6") (pin "51") (pinfunction "PA20_51") (pintype "bidirectional"))
    )
    (net (code "114") (name "~{NRF_RESET}") (class "Default")
      (node (ref "J3") (pin "2") (pinfunction "SWDIO_2") (pintype "bidirectional"))
      (node (ref "U5") (pin "23") (pinfunction "SWDIO/~{RESET}_23") (pintype "bidirectional"))
      (node (ref "U6") (pin "44") (pinfunction "PA17_44") (pintype "bidirectional"))
    )
    (net (code "115") (name "~{SAM4L_RESET}") (class "Default")
      (node (ref "J2") (pin "3") (pinfunction "~{RESET}_3") (pintype "bidirectional"))
      (node (ref "JP4") (pin "11") (pinfunction "11_11") (pintype "passive"))
      (node (ref "S1") (pin "1") (pinfunction "P$1_1") (pintype "passive"))
      (node (ref "U1") (pin "18") (pinfunction "~{DTR}_18") (pintype "bidirectional"))
      (node (ref "U6") (pin "4") (pinfunction "~{RESET}_4") (pintype "bidirectional"))
    )
  )
)
